# fat_pannal.net
KiCad netlist of a schematic drawn in EAGLE
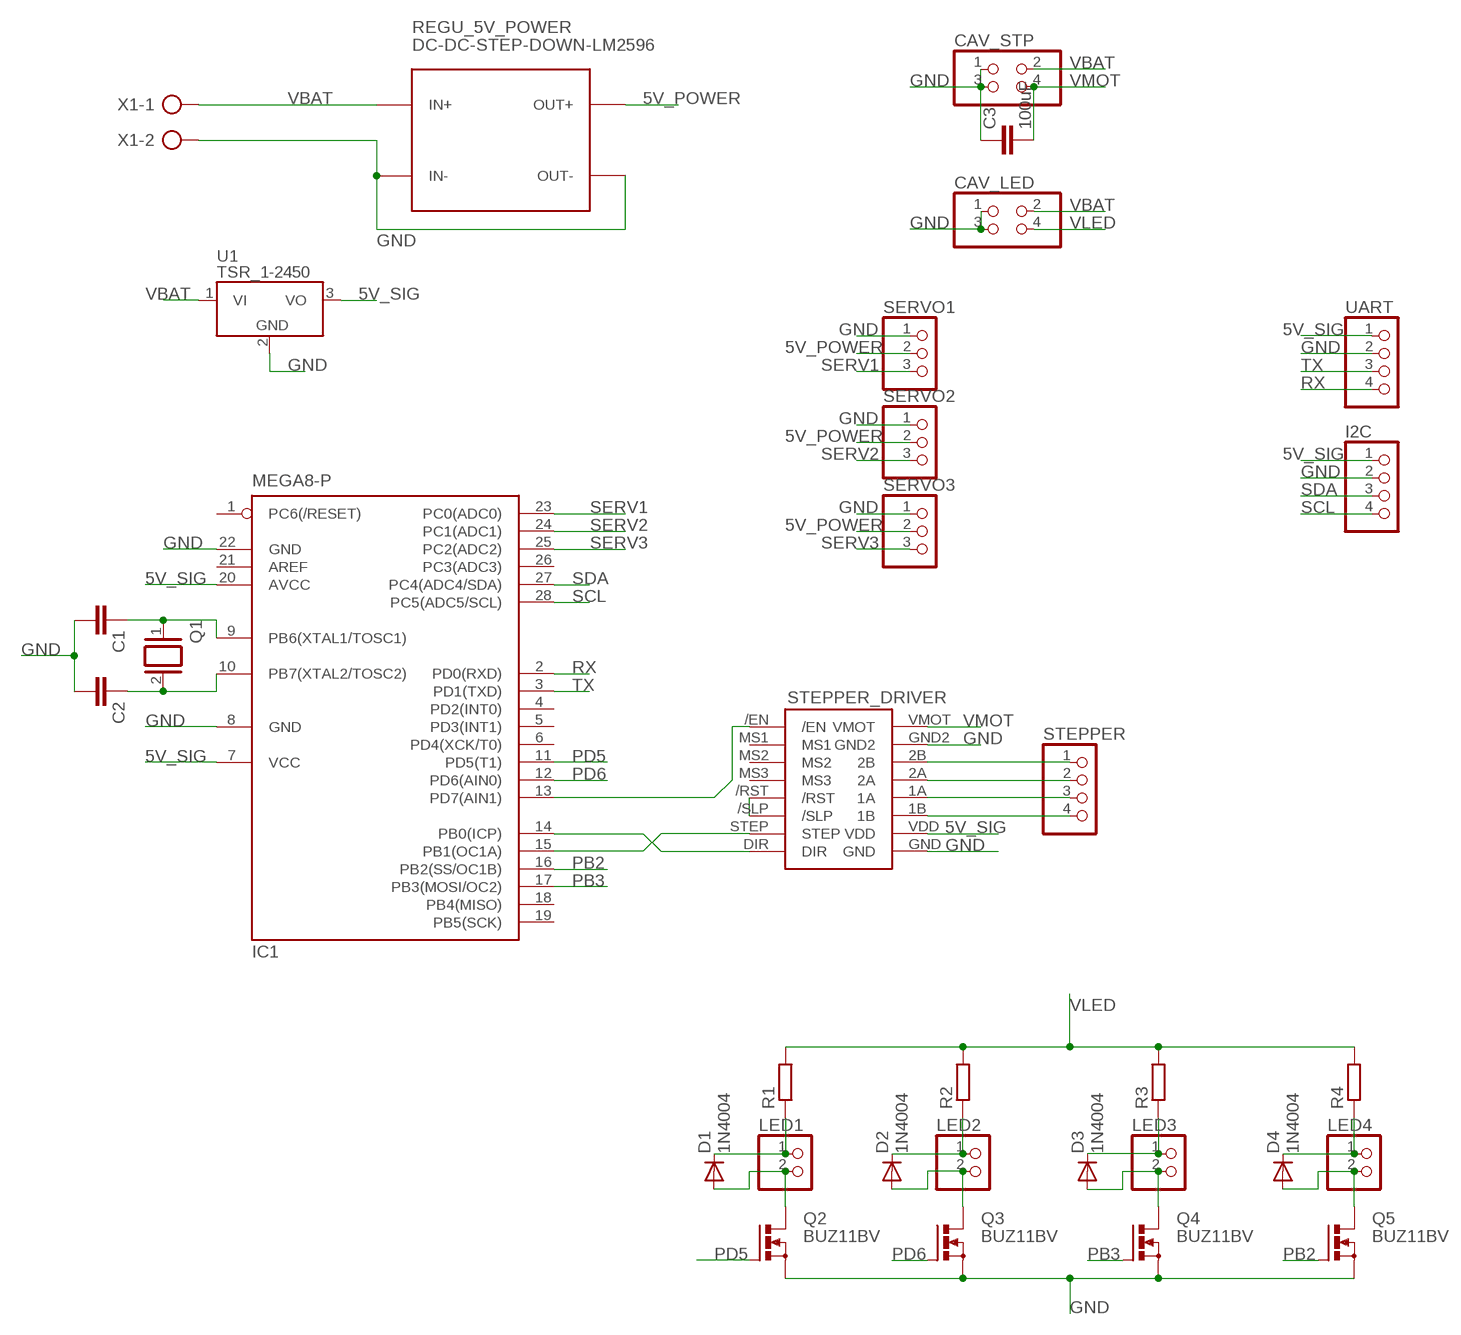
[diagram p0: schematic, sheet 1]

(export (version "E")
  (design (tool "Eeschema 10.0.6"))
  (components
    (comp (ref "C1")
      (value "C-EU025-030X050")
      (footprint "eagle-import:C025-030X050")
      (libsource (lib "eagle-import") (part "C-EU025-030X050"))
    )
    (comp (ref "C2")
      (value "C-EU025-030X050")
      (footprint "eagle-import:C025-030X050")
      (libsource (lib "eagle-import") (part "C-EU025-030X050"))
    )
    (comp (ref "C3")
      (value "100uF")
      (footprint "eagle-import:C025-050X050")
      (libsource (lib "eagle-import") (part "C-EU025-050X050"))
    )
    (comp (ref "CAV_LED")
      (value "PINHD-2X2")
      (footprint "eagle-import:2X02")
      (libsource (lib "eagle-import") (part "PINHD-2X2"))
    )
    (comp (ref "CAV_STP")
      (value "PINHD-2X2")
      (footprint "eagle-import:2X02")
      (libsource (lib "eagle-import") (part "PINHD-2X2"))
    )
    (comp (ref "D1")
      (value "1N4004")
      (footprint "eagle-import:DO41-10")
      (libsource (lib "eagle-import") (part "1N4004"))
    )
    (comp (ref "D2")
      (value "1N4004")
      (footprint "eagle-import:DO41-10")
      (libsource (lib "eagle-import") (part "1N4004"))
    )
    (comp (ref "D3")
      (value "1N4004")
      (footprint "eagle-import:DO41-10")
      (libsource (lib "eagle-import") (part "1N4004"))
    )
    (comp (ref "D4")
      (value "1N4004")
      (footprint "eagle-import:DO41-10")
      (libsource (lib "eagle-import") (part "1N4004"))
    )
    (comp (ref "I2C")
      (value "PINHD-1X4")
      (footprint "eagle-import:1X04")
      (libsource (lib "eagle-import") (part "PINHD-1X4"))
    )
    (comp (ref "IC1")
      (value "MEGA8-P")
      (footprint "eagle-import:DIL28-3")
      (libsource (lib "eagle-import") (part "MEGA8-P"))
    )
    (comp (ref "LED1")
      (value "PINHD-1X2")
      (footprint "eagle-import:1X02")
      (libsource (lib "eagle-import") (part "PINHD-1X2"))
    )
    (comp (ref "LED2")
      (value "PINHD-1X2")
      (footprint "eagle-import:1X02")
      (libsource (lib "eagle-import") (part "PINHD-1X2"))
    )
    (comp (ref "LED3")
      (value "PINHD-1X2")
      (footprint "eagle-import:1X02")
      (libsource (lib "eagle-import") (part "PINHD-1X2"))
    )
    (comp (ref "LED4")
      (value "PINHD-1X2")
      (footprint "eagle-import:1X02")
      (libsource (lib "eagle-import") (part "PINHD-1X2"))
    )
    (comp (ref "Q1")
      (value "XTAL/S")
      (footprint "eagle-import:QS")
      (libsource (lib "eagle-import") (part "XTAL/S"))
    )
    (comp (ref "Q2")
      (value "BUZ11BV")
      (footprint "eagle-import:TO220BV")
      (libsource (lib "eagle-import") (part "BUZ11BV"))
    )
    (comp (ref "Q3")
      (value "BUZ11BV")
      (footprint "eagle-import:TO220BV")
      (libsource (lib "eagle-import") (part "BUZ11BV"))
    )
    (comp (ref "Q4")
      (value "BUZ11BV")
      (footprint "eagle-import:TO220BV")
      (libsource (lib "eagle-import") (part "BUZ11BV"))
    )
    (comp (ref "Q5")
      (value "BUZ11BV")
      (footprint "eagle-import:TO220BV")
      (libsource (lib "eagle-import") (part "BUZ11BV"))
    )
    (comp (ref "R1")
      (value "R-EU_0309/12")
      (footprint "eagle-import:0309_12")
      (libsource (lib "eagle-import") (part "R-EU_0309/12"))
    )
    (comp (ref "R2")
      (value "R-EU_0309/12")
      (footprint "eagle-import:0309_12")
      (libsource (lib "eagle-import") (part "R-EU_0309/12"))
    )
    (comp (ref "R3")
      (value "R-EU_0309/12")
      (footprint "eagle-import:0309_12")
      (libsource (lib "eagle-import") (part "R-EU_0309/12"))
    )
    (comp (ref "R4")
      (value "R-EU_0309/12")
      (footprint "eagle-import:0309_12")
      (libsource (lib "eagle-import") (part "R-EU_0309/12"))
    )
    (comp (ref "REGU_5V_POWER")
      (value "DC-DC-STEP-DOWN-LM2596")
      (footprint "eagle-import:DC-DC-STEP-DOWN-LM2596")
      (libsource (lib "eagle-import") (part "DC-DC-STEP-DOWN-LM2596"))
    )
    (comp (ref "SERVO1")
      (value "PINHD-1X3")
      (footprint "eagle-import:1X03")
      (libsource (lib "eagle-import") (part "PINHD-1X3"))
    )
    (comp (ref "SERVO2")
      (value "PINHD-1X3")
      (footprint "eagle-import:1X03")
      (libsource (lib "eagle-import") (part "PINHD-1X3"))
    )
    (comp (ref "SERVO3")
      (value "PINHD-1X3")
      (footprint "eagle-import:1X03")
      (libsource (lib "eagle-import") (part "PINHD-1X3"))
    )
    (comp (ref "STEPPER")
      (value "PINHD-1X4")
      (footprint "eagle-import:1X04")
      (libsource (lib "eagle-import") (part "PINHD-1X4"))
    )
    (comp (ref "STEPPER_DRIVER")
      (value "A4988_CARRIER")
      (footprint "eagle-import:A4988_CARRIER")
      (libsource (lib "eagle-import") (part "A4988_CARRIER"))
    )
    (comp (ref "U1")
      (value "TSR_1-2450")
      (footprint "eagle-import:TSR-1")
      (libsource (lib "eagle-import") (part "TSR_1-2450"))
    )
    (comp (ref "UART")
      (value "PINHD-1X4")
      (footprint "eagle-import:1X04")
      (libsource (lib "eagle-import") (part "PINHD-1X4"))
    )
    (comp (ref "X1")
      (value "AK300/2")
      (footprint "eagle-import:AK300_2")
      (libsource (lib "eagle-import") (part "AK300/2"))
    )
  )
  (nets
    (net (code "1") (name "/5V_POWER") (class "Default")
      (node (ref "REGU_5V_POWER") (pin "OUT+") (pinfunction "OUT+_OUT+") (pintype "bidirectional"))
      (node (ref "SERVO1") (pin "2") (pinfunction "2_2") (pintype "passive"))
      (node (ref "SERVO2") (pin "2") (pinfunction "2_2") (pintype "passive"))
      (node (ref "SERVO3") (pin "2") (pinfunction "2_2") (pintype "passive"))
    )
    (net (code "2") (name "/5V_SIG") (class "Default")
      (node (ref "I2C") (pin "1") (pinfunction "1_1") (pintype "passive"))
      (node (ref "IC1") (pin "20") (pinfunction "AVCC_20") (pintype "power_in"))
      (node (ref "IC1") (pin "7") (pinfunction "VCC_7") (pintype "power_in"))
      (node (ref "STEPPER_DRIVER") (pin "VDD") (pinfunction "VDD_VDD") (pintype "bidirectional"))
      (node (ref "U1") (pin "3") (pinfunction "VO_3") (pintype "power_in"))
      (node (ref "UART") (pin "1") (pinfunction "1_1") (pintype "passive"))
    )
    (net (code "3") (name "/GND") (class "Default")
      (node (ref "C1") (pin "2") (pinfunction "2_2") (pintype "passive"))
      (node (ref "C2") (pin "2") (pinfunction "2_2") (pintype "passive"))
      (node (ref "C3") (pin "1") (pinfunction "1_1") (pintype "passive"))
      (node (ref "CAV_LED") (pin "1") (pinfunction "1_1") (pintype "passive"))
      (node (ref "CAV_LED") (pin "3") (pinfunction "3_3") (pintype "passive"))
      (node (ref "CAV_STP") (pin "1") (pinfunction "1_1") (pintype "passive"))
      (node (ref "CAV_STP") (pin "3") (pinfunction "3_3") (pintype "passive"))
      (node (ref "I2C") (pin "2") (pinfunction "2_2") (pintype "passive"))
      (node (ref "IC1") (pin "22") (pinfunction "GND_22") (pintype "power_in"))
      (node (ref "IC1") (pin "8") (pinfunction "GND_8") (pintype "power_in"))
      (node (ref "Q2") (pin "S") (pinfunction "S_S") (pintype "passive"))
      (node (ref "Q3") (pin "S") (pinfunction "S_S") (pintype "passive"))
      (node (ref "Q4") (pin "S") (pinfunction "S_S") (pintype "passive"))
      (node (ref "Q5") (pin "S") (pinfunction "S_S") (pintype "passive"))
      (node (ref "REGU_5V_POWER") (pin "IN-") (pinfunction "IN-_IN-") (pintype "bidirectional"))
      (node (ref "REGU_5V_POWER") (pin "OUT-") (pinfunction "OUT-_OUT-") (pintype "bidirectional"))
      (node (ref "SERVO1") (pin "1") (pinfunction "1_1") (pintype "passive"))
      (node (ref "SERVO2") (pin "1") (pinfunction "1_1") (pintype "passive"))
      (node (ref "SERVO3") (pin "1") (pinfunction "1_1") (pintype "passive"))
      (node (ref "STEPPER_DRIVER") (pin "GND") (pinfunction "GND_GND") (pintype "bidirectional"))
      (node (ref "STEPPER_DRIVER") (pin "GND2") (pinfunction "GND2_GND2") (pintype "bidirectional"))
      (node (ref "U1") (pin "2") (pinfunction "GND_2") (pintype "power_in"))
      (node (ref "UART") (pin "2") (pinfunction "2_2") (pintype "passive"))
      (node (ref "X1") (pin "2") (pinfunction "KL_2") (pintype "passive"))
    )
    (net (code "4") (name "/PB2") (class "Default")
      (node (ref "IC1") (pin "16") (pinfunction "PB2(SS/OC1B)_16") (pintype "bidirectional"))
      (node (ref "Q5") (pin "G") (pinfunction "G_G") (pintype "passive"))
    )
    (net (code "5") (name "/PB3") (class "Default")
      (node (ref "IC1") (pin "17") (pinfunction "PB3(MOSI/OC2)_17") (pintype "bidirectional"))
      (node (ref "Q4") (pin "G") (pinfunction "G_G") (pintype "passive"))
    )
    (net (code "6") (name "/PD5") (class "Default")
      (node (ref "IC1") (pin "11") (pinfunction "PD5(T1)_11") (pintype "bidirectional"))
      (node (ref "Q2") (pin "G") (pinfunction "G_G") (pintype "passive"))
    )
    (net (code "7") (name "/PD6") (class "Default")
      (node (ref "IC1") (pin "12") (pinfunction "PD6(AIN0)_12") (pintype "bidirectional"))
      (node (ref "Q3") (pin "G") (pinfunction "G_G") (pintype "passive"))
    )
    (net (code "8") (name "/RX") (class "Default")
      (node (ref "IC1") (pin "2") (pinfunction "PD0(RXD)_2") (pintype "bidirectional"))
      (node (ref "UART") (pin "4") (pinfunction "4_4") (pintype "passive"))
    )
    (net (code "9") (name "/SCL") (class "Default")
      (node (ref "I2C") (pin "4") (pinfunction "4_4") (pintype "passive"))
      (node (ref "IC1") (pin "28") (pinfunction "PC5(ADC5/SCL)_28") (pintype "bidirectional"))
    )
    (net (code "10") (name "/SDA") (class "Default")
      (node (ref "I2C") (pin "3") (pinfunction "3_3") (pintype "passive"))
      (node (ref "IC1") (pin "27") (pinfunction "PC4(ADC4/SDA)_27") (pintype "bidirectional"))
    )
    (net (code "11") (name "/SERV1") (class "Default")
      (node (ref "IC1") (pin "23") (pinfunction "PC0(ADC0)_23") (pintype "bidirectional"))
      (node (ref "SERVO1") (pin "3") (pinfunction "3_3") (pintype "passive"))
    )
    (net (code "12") (name "/SERV2") (class "Default")
      (node (ref "IC1") (pin "24") (pinfunction "PC1(ADC1)_24") (pintype "bidirectional"))
      (node (ref "SERVO2") (pin "3") (pinfunction "3_3") (pintype "passive"))
    )
    (net (code "13") (name "/SERV3") (class "Default")
      (node (ref "IC1") (pin "25") (pinfunction "PC2(ADC2)_25") (pintype "bidirectional"))
      (node (ref "SERVO3") (pin "3") (pinfunction "3_3") (pintype "passive"))
    )
    (net (code "14") (name "/TX") (class "Default")
      (node (ref "IC1") (pin "3") (pinfunction "PD1(TXD)_3") (pintype "bidirectional"))
      (node (ref "UART") (pin "3") (pinfunction "3_3") (pintype "passive"))
    )
    (net (code "15") (name "/VBAT") (class "Default")
      (node (ref "CAV_LED") (pin "2") (pinfunction "2_2") (pintype "passive"))
      (node (ref "CAV_STP") (pin "2") (pinfunction "2_2") (pintype "passive"))
      (node (ref "REGU_5V_POWER") (pin "IN+") (pinfunction "IN+_IN+") (pintype "bidirectional"))
      (node (ref "U1") (pin "1") (pinfunction "VI_1") (pintype "power_in"))
      (node (ref "X1") (pin "1") (pinfunction "KL_1") (pintype "passive"))
    )
    (net (code "16") (name "/VLED") (class "Default")
      (node (ref "CAV_LED") (pin "4") (pinfunction "4_4") (pintype "passive"))
      (node (ref "R1") (pin "2") (pinfunction "2_2") (pintype "passive"))
      (node (ref "R2") (pin "2") (pinfunction "2_2") (pintype "passive"))
      (node (ref "R3") (pin "2") (pinfunction "2_2") (pintype "passive"))
      (node (ref "R4") (pin "2") (pinfunction "2_2") (pintype "passive"))
    )
    (net (code "17") (name "/VMOT") (class "Default")
      (node (ref "C3") (pin "2") (pinfunction "2_2") (pintype "passive"))
      (node (ref "CAV_STP") (pin "4") (pinfunction "4_4") (pintype "passive"))
      (node (ref "STEPPER_DRIVER") (pin "VMOT") (pinfunction "VMOT_VMOT") (pintype "bidirectional"))
    )
    (net (code "18") (name "Net-(D1-PadA)") (class "Default")
      (node (ref "D1") (pin "A") (pinfunction "A_A") (pintype "passive"))
      (node (ref "LED1") (pin "2") (pinfunction "2_2") (pintype "passive"))
      (node (ref "Q2") (pin "D") (pinfunction "D_D") (pintype "passive"))
    )
    (net (code "19") (name "Net-(D1-PadC)") (class "Default")
      (node (ref "D1") (pin "C") (pinfunction "C_C") (pintype "passive"))
      (node (ref "LED1") (pin "1") (pinfunction "1_1") (pintype "passive"))
      (node (ref "R1") (pin "1") (pinfunction "1_1") (pintype "passive"))
    )
    (net (code "20") (name "Net-(D2-PadA)") (class "Default")
      (node (ref "D2") (pin "A") (pinfunction "A_A") (pintype "passive"))
      (node (ref "LED2") (pin "2") (pinfunction "2_2") (pintype "passive"))
      (node (ref "Q3") (pin "D") (pinfunction "D_D") (pintype "passive"))
    )
    (net (code "21") (name "Net-(D2-PadC)") (class "Default")
      (node (ref "D2") (pin "C") (pinfunction "C_C") (pintype "passive"))
      (node (ref "LED2") (pin "1") (pinfunction "1_1") (pintype "passive"))
      (node (ref "R2") (pin "1") (pinfunction "1_1") (pintype "passive"))
    )
    (net (code "22") (name "Net-(D3-PadA)") (class "Default")
      (node (ref "D3") (pin "A") (pinfunction "A_A") (pintype "passive"))
      (node (ref "LED3") (pin "2") (pinfunction "2_2") (pintype "passive"))
      (node (ref "Q4") (pin "D") (pinfunction "D_D") (pintype "passive"))
    )
    (net (code "23") (name "Net-(D3-PadC)") (class "Default")
      (node (ref "D3") (pin "C") (pinfunction "C_C") (pintype "passive"))
      (node (ref "LED3") (pin "1") (pinfunction "1_1") (pintype "passive"))
      (node (ref "R3") (pin "1") (pinfunction "1_1") (pintype "passive"))
    )
    (net (code "24") (name "Net-(D4-PadA)") (class "Default")
      (node (ref "D4") (pin "A") (pinfunction "A_A") (pintype "passive"))
      (node (ref "LED4") (pin "2") (pinfunction "2_2") (pintype "passive"))
      (node (ref "Q5") (pin "D") (pinfunction "D_D") (pintype "passive"))
    )
    (net (code "25") (name "Net-(D4-PadC)") (class "Default")
      (node (ref "D4") (pin "C") (pinfunction "C_C") (pintype "passive"))
      (node (ref "LED4") (pin "1") (pinfunction "1_1") (pintype "passive"))
      (node (ref "R4") (pin "1") (pinfunction "1_1") (pintype "passive"))
    )
    (net (code "26") (name "Net-(IC1-PB0(ICP))") (class "Default")
      (node (ref "IC1") (pin "14") (pinfunction "PB0(ICP)_14") (pintype "bidirectional"))
      (node (ref "STEPPER_DRIVER") (pin "DIR") (pinfunction "DIR_DIR") (pintype "bidirectional"))
    )
    (net (code "27") (name "Net-(IC1-PB1(OC1A))") (class "Default")
      (node (ref "IC1") (pin "15") (pinfunction "PB1(OC1A)_15") (pintype "bidirectional"))
      (node (ref "STEPPER_DRIVER") (pin "STEP") (pinfunction "STEP_STEP") (pintype "bidirectional"))
    )
    (net (code "28") (name "Net-(IC1-PB6(XTAL1{slash}TOSC1))") (class "Default")
      (node (ref "C1") (pin "1") (pinfunction "1_1") (pintype "passive"))
      (node (ref "IC1") (pin "9") (pinfunction "PB6(XTAL1/TOSC1)_9") (pintype "bidirectional"))
      (node (ref "Q1") (pin "1") (pinfunction "1_1") (pintype "passive"))
    )
    (net (code "29") (name "Net-(IC1-PB7(XTAL2{slash}TOSC2))") (class "Default")
      (node (ref "C2") (pin "1") (pinfunction "1_1") (pintype "passive"))
      (node (ref "IC1") (pin "10") (pinfunction "PB7(XTAL2/TOSC2)_10") (pintype "bidirectional"))
      (node (ref "Q1") (pin "2") (pinfunction "2_2") (pintype "passive"))
    )
    (net (code "30") (name "Net-(IC1-PD7(AIN1))") (class "Default")
      (node (ref "IC1") (pin "13") (pinfunction "PD7(AIN1)_13") (pintype "bidirectional"))
      (node (ref "STEPPER_DRIVER") (pin "/EN") (pinfunction "/EN_/EN") (pintype "bidirectional"))
    )
    (net (code "31") (name "Net-(STEPPER-Pad1)") (class "Default")
      (node (ref "STEPPER") (pin "1") (pinfunction "1_1") (pintype "passive"))
      (node (ref "STEPPER_DRIVER") (pin "2B") (pinfunction "2B_2B") (pintype "bidirectional"))
    )
    (net (code "32") (name "Net-(STEPPER-Pad2)") (class "Default")
      (node (ref "STEPPER") (pin "2") (pinfunction "2_2") (pintype "passive"))
      (node (ref "STEPPER_DRIVER") (pin "2A") (pinfunction "2A_2A") (pintype "bidirectional"))
    )
    (net (code "33") (name "Net-(STEPPER-Pad3)") (class "Default")
      (node (ref "STEPPER") (pin "3") (pinfunction "3_3") (pintype "passive"))
      (node (ref "STEPPER_DRIVER") (pin "1A") (pinfunction "1A_1A") (pintype "bidirectional"))
    )
    (net (code "34") (name "Net-(STEPPER-Pad4)") (class "Default")
      (node (ref "STEPPER") (pin "4") (pinfunction "4_4") (pintype "passive"))
      (node (ref "STEPPER_DRIVER") (pin "1B") (pinfunction "1B_1B") (pintype "bidirectional"))
    )
    (net (code "35") (name "Net-(STEPPER_DRIVER-Pad{slash}RST)") (class "Default")
      (node (ref "STEPPER_DRIVER") (pin "/RST") (pinfunction "/RST_/RST") (pintype "bidirectional"))
      (node (ref "STEPPER_DRIVER") (pin "/SLP") (pinfunction "/SLP_/SLP") (pintype "bidirectional"))
    )
    (net (code "36") (name "unconnected-(IC1-AREF-Pad21)") (class "Default")
      (node (ref "IC1") (pin "21") (pinfunction "AREF_21") (pintype "passive"))
    )
    (net (code "37") (name "unconnected-(IC1-PB4(MISO)-Pad18)") (class "Default")
      (node (ref "IC1") (pin "18") (pinfunction "PB4(MISO)_18") (pintype "bidirectional"))
    )
    (net (code "38") (name "unconnected-(IC1-PB5(SCK)-Pad19)") (class "Default")
      (node (ref "IC1") (pin "19") (pinfunction "PB5(SCK)_19") (pintype "bidirectional"))
    )
    (net (code "39") (name "unconnected-(IC1-PC3(ADC3)-Pad26)") (class "Default")
      (node (ref "IC1") (pin "26") (pinfunction "PC3(ADC3)_26") (pintype "bidirectional"))
    )
    (net (code "40") (name "unconnected-(IC1-PC6({slash}RESET)-Pad1)") (class "Default")
      (node (ref "IC1") (pin "1") (pinfunction "PC6(/RESET)_1") (pintype "bidirectional"))
    )
    (net (code "41") (name "unconnected-(IC1-PD2(INT0)-Pad4)") (class "Default")
      (node (ref "IC1") (pin "4") (pinfunction "PD2(INT0)_4") (pintype "bidirectional"))
    )
    (net (code "42") (name "unconnected-(IC1-PD3(INT1)-Pad5)") (class "Default")
      (node (ref "IC1") (pin "5") (pinfunction "PD3(INT1)_5") (pintype "bidirectional"))
    )
    (net (code "43") (name "unconnected-(IC1-PD4(XCK{slash}T0)-Pad6)") (class "Default")
      (node (ref "IC1") (pin "6") (pinfunction "PD4(XCK/T0)_6") (pintype "bidirectional"))
    )
    (net (code "44") (name "unconnected-(STEPPER_DRIVER-PadMS1)") (class "Default")
      (node (ref "STEPPER_DRIVER") (pin "MS1") (pinfunction "MS1_MS1") (pintype "bidirectional"))
    )
    (net (code "45") (name "unconnected-(STEPPER_DRIVER-PadMS2)") (class "Default")
      (node (ref "STEPPER_DRIVER") (pin "MS2") (pinfunction "MS2_MS2") (pintype "bidirectional"))
    )
    (net (code "46") (name "unconnected-(STEPPER_DRIVER-PadMS3)") (class "Default")
      (node (ref "STEPPER_DRIVER") (pin "MS3") (pinfunction "MS3_MS3") (pintype "bidirectional"))
    )
  )
)
